# HeadsetCCup.net
KiCad netlist of a schematic drawn in EAGLE
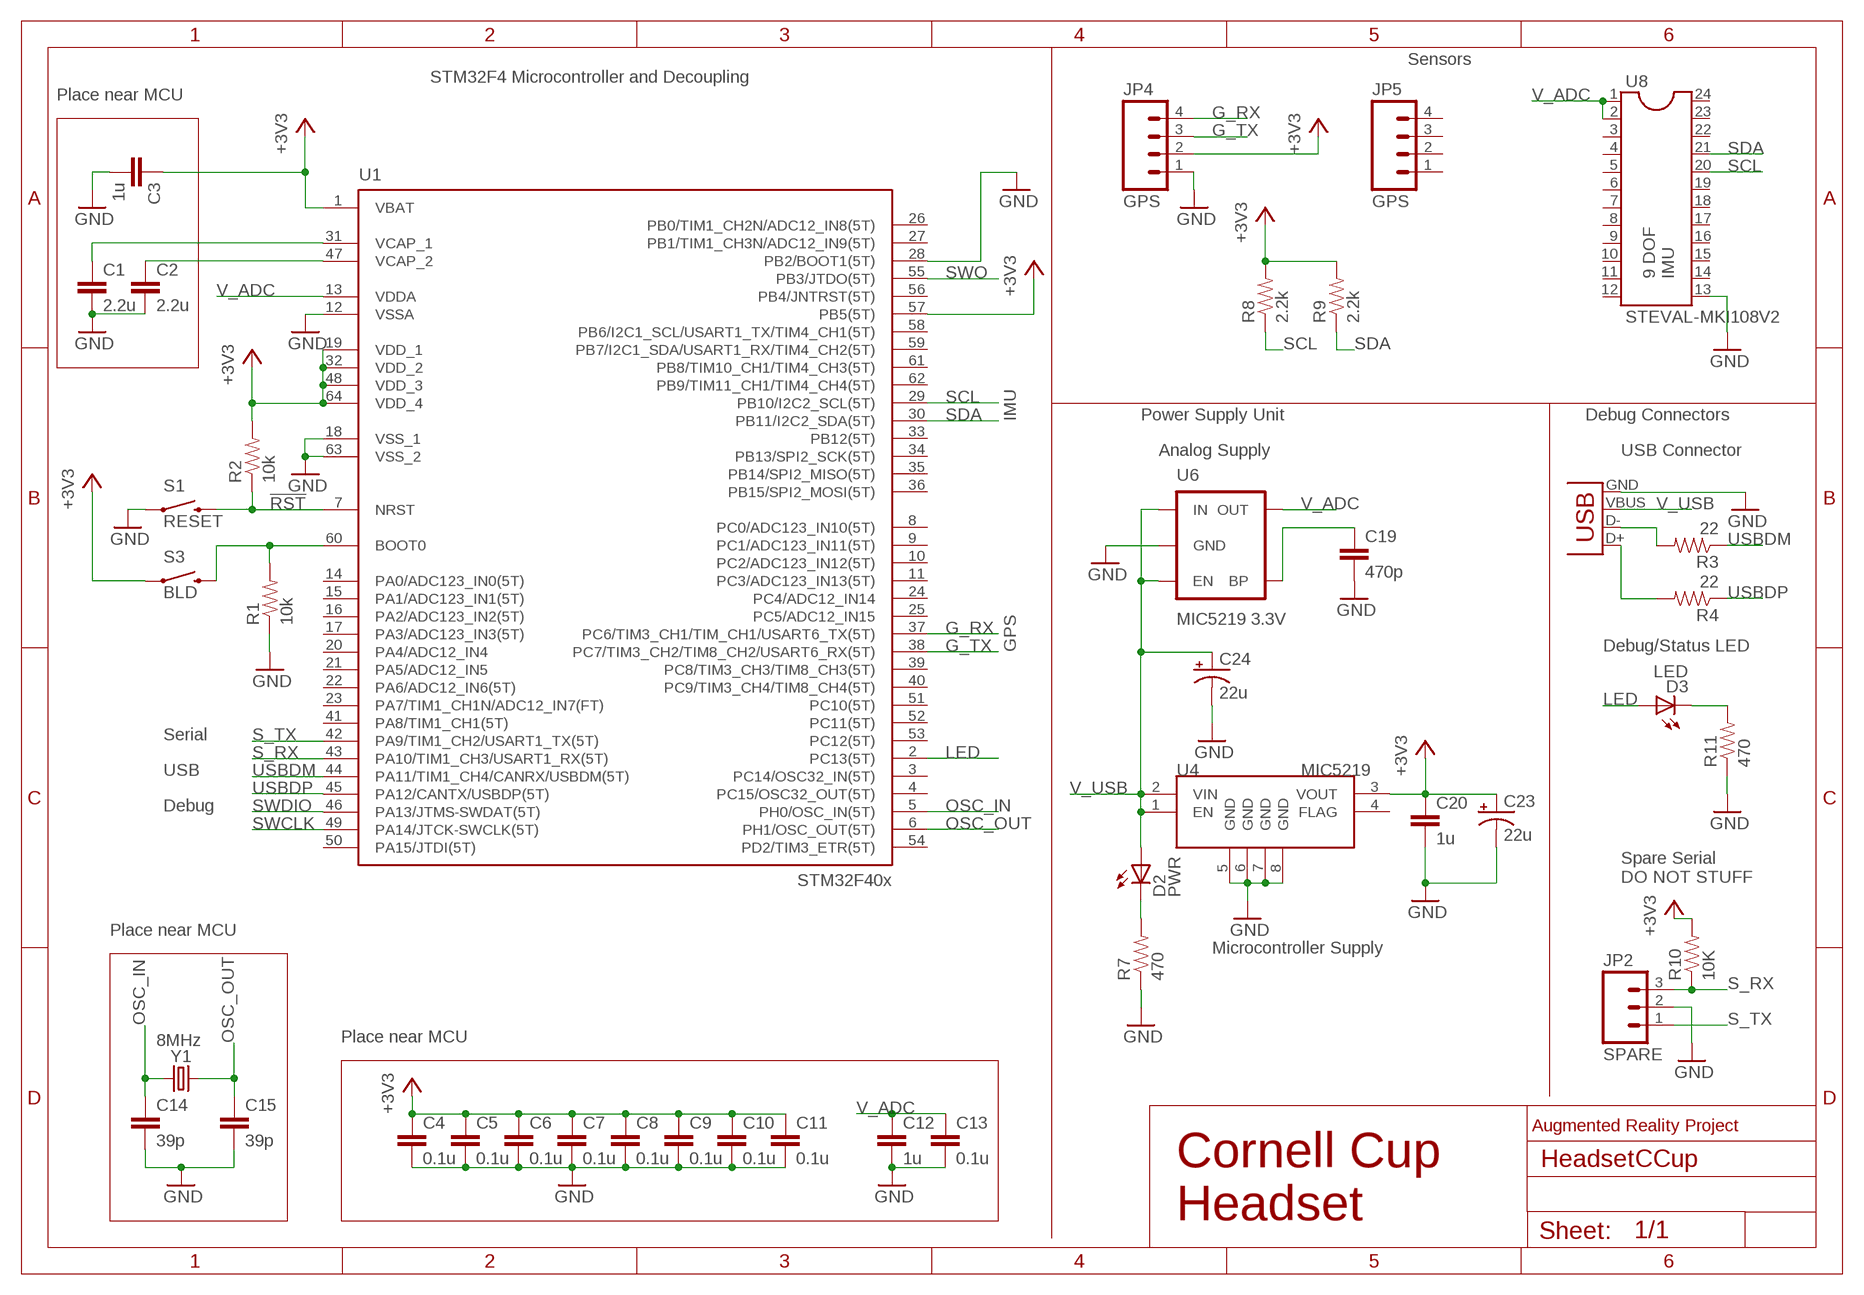
[diagram p0: schematic, sheet 1]

(export (version "E")
  (design (tool "Eeschema 10.0.6"))
  (components
    (comp (ref "C1")
      (value "2.2u")
      (footprint "eagle-import:1206")
      (libsource (lib "eagle-import") (part "CAP1206"))
    )
    (comp (ref "C2")
      (value "2.2u")
      (footprint "eagle-import:1206")
      (libsource (lib "eagle-import") (part "CAP1206"))
    )
    (comp (ref "C3")
      (value "1u")
      (footprint "eagle-import:1206")
      (libsource (lib "eagle-import") (part "CAP1206"))
    )
    (comp (ref "C4")
      (value "0.1u")
      (footprint "eagle-import:1206")
      (libsource (lib "eagle-import") (part "CAP1206"))
    )
    (comp (ref "C5")
      (value "0.1u")
      (footprint "eagle-import:1206")
      (libsource (lib "eagle-import") (part "CAP1206"))
    )
    (comp (ref "C6")
      (value "0.1u")
      (footprint "eagle-import:1206")
      (libsource (lib "eagle-import") (part "CAP1206"))
    )
    (comp (ref "C7")
      (value "0.1u")
      (footprint "eagle-import:1206")
      (libsource (lib "eagle-import") (part "CAP1206"))
    )
    (comp (ref "C8")
      (value "0.1u")
      (footprint "eagle-import:1206")
      (libsource (lib "eagle-import") (part "CAP1206"))
    )
    (comp (ref "C9")
      (value "0.1u")
      (footprint "eagle-import:1206")
      (libsource (lib "eagle-import") (part "CAP1206"))
    )
    (comp (ref "C10")
      (value "0.1u")
      (footprint "eagle-import:1206")
      (libsource (lib "eagle-import") (part "CAP1206"))
    )
    (comp (ref "C11")
      (value "0.1u")
      (footprint "eagle-import:1206")
      (libsource (lib "eagle-import") (part "CAP1206"))
    )
    (comp (ref "C12")
      (value "1u")
      (footprint "eagle-import:1206")
      (libsource (lib "eagle-import") (part "CAP1206"))
    )
    (comp (ref "C13")
      (value "0.1u")
      (footprint "eagle-import:1206")
      (libsource (lib "eagle-import") (part "CAP1206"))
    )
    (comp (ref "C14")
      (value "39p")
      (footprint "eagle-import:1206")
      (libsource (lib "eagle-import") (part "CAP1206"))
    )
    (comp (ref "C15")
      (value "39p")
      (footprint "eagle-import:1206")
      (libsource (lib "eagle-import") (part "CAP1206"))
    )
    (comp (ref "C19")
      (value "470p")
      (footprint "eagle-import:1206")
      (libsource (lib "eagle-import") (part "CAP1206"))
    )
    (comp (ref "C20")
      (value "1u")
      (footprint "eagle-import:1206")
      (libsource (lib "eagle-import") (part "CAP1206"))
    )
    (comp (ref "C23")
      (value "22u")
      (footprint "eagle-import:PANASONIC_D")
      (libsource (lib "eagle-import") (part "CAP_POLD"))
    )
    (comp (ref "C24")
      (value "22u")
      (footprint "eagle-import:PANASONIC_D")
      (libsource (lib "eagle-import") (part "CAP_POLD"))
    )
    (comp (ref "D2")
      (value "PWR")
      (footprint "eagle-import:LED-1206")
      (libsource (lib "eagle-import") (part "LED-RED1206"))
    )
    (comp (ref "D3")
      (value "LED")
      (footprint "eagle-import:LED-1206")
      (libsource (lib "eagle-import") (part "LED-RED1206"))
    )
    (comp (ref "JP1")
      (value "USBSMD")
      (footprint "eagle-import:USB-MINIB")
      (libsource (lib "eagle-import") (part "USBSMD"))
    )
    (comp (ref "JP2")
      (value "SPARE")
      (footprint "eagle-import:1X03")
      (libsource (lib "eagle-import") (part "M03PTH"))
    )
    (comp (ref "JP4")
      (value "GPS")
      (footprint "eagle-import:1X04")
      (libsource (lib "eagle-import") (part "M04PTH"))
    )
    (comp (ref "JP5")
      (value "GPS")
      (footprint "eagle-import:1X04")
      (libsource (lib "eagle-import") (part "M04PTH"))
    )
    (comp (ref "R1")
      (value "10k")
      (footprint "eagle-import:1206")
      (libsource (lib "eagle-import") (part "RES1206"))
    )
    (comp (ref "R2")
      (value "10k")
      (footprint "eagle-import:1206")
      (libsource (lib "eagle-import") (part "RES1206"))
    )
    (comp (ref "R3")
      (value "22")
      (footprint "eagle-import:1206")
      (libsource (lib "eagle-import") (part "RES1206"))
    )
    (comp (ref "R4")
      (value "22")
      (footprint "eagle-import:1206")
      (libsource (lib "eagle-import") (part "RES1206"))
    )
    (comp (ref "R7")
      (value "470")
      (footprint "eagle-import:1206")
      (libsource (lib "eagle-import") (part "RES1206"))
    )
    (comp (ref "R8")
      (value "2.2k")
      (footprint "eagle-import:1206")
      (libsource (lib "eagle-import") (part "RES1206"))
    )
    (comp (ref "R9")
      (value "2.2k")
      (footprint "eagle-import:1206")
      (libsource (lib "eagle-import") (part "RES1206"))
    )
    (comp (ref "R10")
      (value "10K")
      (footprint "eagle-import:1206")
      (libsource (lib "eagle-import") (part "RES1206"))
    )
    (comp (ref "R11")
      (value "470")
      (footprint "eagle-import:1206")
      (libsource (lib "eagle-import") (part "RES1206"))
    )
    (comp (ref "S1")
      (value "RESET")
      (footprint "eagle-import:TACTILE-PTH")
      (libsource (lib "eagle-import") (part "SWITCH-MOMENTARY-2PTH"))
    )
    (comp (ref "S3")
      (value "BLD")
      (footprint "eagle-import:TACTILE-PTH")
      (libsource (lib "eagle-import") (part "SWITCH-MOMENTARY-2PTH"))
    )
    (comp (ref "U1")
      (value "STM32F405RGT6")
      (footprint "eagle-import:TQFP64")
      (libsource (lib "eagle-import") (part "STM32F405R"))
    )
    (comp (ref "U4")
      (value "MIC5219")
      (footprint "eagle-import:MSOP8")
      (libsource (lib "eagle-import") (part "V_REG_MIC5216"))
    )
    (comp (ref "U6")
      (value "MIC5219 3.3V")
      (footprint "eagle-import:SOT23-5")
      (libsource (lib "eagle-import") (part "V_REG_MIC52193.3V"))
    )
    (comp (ref "U8")
      (value "STEVAL-MKI108V2")
      (footprint "eagle-import:DIL24-6")
      (libsource (lib "eagle-import") (part "DIL24-6"))
    )
    (comp (ref "Y1")
      (value "8MHz")
      (footprint "eagle-import:HC49US")
      (libsource (lib "eagle-import") (part "CRYSTALHC49US"))
    )
  )
  (nets
    (net (code "1") (name "+3V3") (class "Default")
      (node (ref "C10") (pin "1") (pinfunction "1_1") (pintype "passive"))
      (node (ref "C11") (pin "1") (pinfunction "1_1") (pintype "passive"))
      (node (ref "C20") (pin "1") (pinfunction "1_1") (pintype "passive"))
      (node (ref "C23") (pin "+") (pinfunction "+_+") (pintype "passive"))
      (node (ref "C3") (pin "1") (pinfunction "1_1") (pintype "passive"))
      (node (ref "C4") (pin "1") (pinfunction "1_1") (pintype "passive"))
      (node (ref "C5") (pin "1") (pinfunction "1_1") (pintype "passive"))
      (node (ref "C6") (pin "1") (pinfunction "1_1") (pintype "passive"))
      (node (ref "C7") (pin "1") (pinfunction "1_1") (pintype "passive"))
      (node (ref "C8") (pin "1") (pinfunction "1_1") (pintype "passive"))
      (node (ref "C9") (pin "1") (pinfunction "1_1") (pintype "passive"))
      (node (ref "JP4") (pin "2") (pinfunction "2_2") (pintype "passive"))
      (node (ref "R10") (pin "2") (pinfunction "2_2") (pintype "passive"))
      (node (ref "R2") (pin "2") (pinfunction "2_2") (pintype "passive"))
      (node (ref "R8") (pin "2") (pinfunction "2_2") (pintype "passive"))
      (node (ref "R9") (pin "2") (pinfunction "2_2") (pintype "passive"))
      (node (ref "S3") (pin "1") (pinfunction "1_1") (pintype "passive"))
      (node (ref "U1") (pin "1") (pinfunction "VBAT_1") (pintype "bidirectional"))
      (node (ref "U1") (pin "19") (pinfunction "VDD_1_19") (pintype "bidirectional"))
      (node (ref "U1") (pin "32") (pinfunction "VDD_2_32") (pintype "bidirectional"))
      (node (ref "U1") (pin "48") (pinfunction "VDD_3_48") (pintype "bidirectional"))
      (node (ref "U1") (pin "57") (pinfunction "PB5(5T)_57") (pintype "bidirectional"))
      (node (ref "U1") (pin "64") (pinfunction "VDD_4_64") (pintype "bidirectional"))
      (node (ref "U4") (pin "3") (pinfunction "VOUT_3") (pintype "bidirectional"))
    )
    (net (code "2") (name "/G_RX") (class "Default")
      (node (ref "JP4") (pin "4") (pinfunction "4_4") (pintype "passive"))
      (node (ref "U1") (pin "37") (pinfunction "PC6/TIM3_CH1/TIM_CH1/USART6_TX(5T)_37") (pintype "bidirectional"))
    )
    (net (code "3") (name "/G_TX") (class "Default")
      (node (ref "JP4") (pin "3") (pinfunction "3_3") (pintype "passive"))
      (node (ref "U1") (pin "38") (pinfunction "PC7/TIM3_CH2/TIM8_CH2/USART6_RX(5T)_38") (pintype "bidirectional"))
    )
    (net (code "4") (name "/LED") (class "Default")
      (node (ref "D3") (pin "A") (pinfunction "A_A") (pintype "passive"))
      (node (ref "U1") (pin "2") (pinfunction "PC13(5T)_2") (pintype "bidirectional"))
    )
    (net (code "5") (name "/OSC_IN") (class "Default")
      (node (ref "C14") (pin "1") (pinfunction "1_1") (pintype "passive"))
      (node (ref "U1") (pin "5") (pinfunction "PH0/OSC_IN(5T)_5") (pintype "bidirectional"))
      (node (ref "Y1") (pin "1") (pinfunction "1_1") (pintype "passive"))
    )
    (net (code "6") (name "/OSC_OUT") (class "Default")
      (node (ref "C15") (pin "1") (pinfunction "1_1") (pintype "passive"))
      (node (ref "U1") (pin "6") (pinfunction "PH1/OSC_OUT(5T)_6") (pintype "bidirectional"))
      (node (ref "Y1") (pin "2") (pinfunction "2_2") (pintype "passive"))
    )
    (net (code "7") (name "/SCL") (class "Default")
      (node (ref "R8") (pin "1") (pinfunction "1_1") (pintype "passive"))
      (node (ref "U1") (pin "29") (pinfunction "PB10/I2C2_SCL(5T)_29") (pintype "bidirectional"))
      (node (ref "U8") (pin "20") (pinfunction "20_20") (pintype "passive"))
    )
    (net (code "8") (name "/SDA") (class "Default")
      (node (ref "R9") (pin "1") (pinfunction "1_1") (pintype "passive"))
      (node (ref "U1") (pin "30") (pinfunction "PB11/I2C2_SDA(5T)_30") (pintype "bidirectional"))
      (node (ref "U8") (pin "21") (pinfunction "21_21") (pintype "passive"))
    )
    (net (code "9") (name "/SWCLK") (class "Default")
      (node (ref "U1") (pin "49") (pinfunction "PA14/JTCK-SWCLK(5T)_49") (pintype "bidirectional"))
    )
    (net (code "10") (name "/SWDIO") (class "Default")
      (node (ref "U1") (pin "46") (pinfunction "PA13/JTMS-SWDAT(5T)_46") (pintype "bidirectional"))
    )
    (net (code "11") (name "/SWO") (class "Default")
      (node (ref "U1") (pin "55") (pinfunction "PB3/JTDO(5T)_55") (pintype "bidirectional"))
    )
    (net (code "12") (name "/S_RX") (class "Default")
      (node (ref "JP2") (pin "3") (pinfunction "3_3") (pintype "passive"))
      (node (ref "R10") (pin "1") (pinfunction "1_1") (pintype "passive"))
      (node (ref "U1") (pin "43") (pinfunction "PA10/TIM1_CH3/USART1_RX(5T)_43") (pintype "bidirectional"))
    )
    (net (code "13") (name "/S_TX") (class "Default")
      (node (ref "JP2") (pin "1") (pinfunction "1_1") (pintype "passive"))
      (node (ref "U1") (pin "42") (pinfunction "PA9/TIM1_CH2/USART1_TX(5T)_42") (pintype "bidirectional"))
    )
    (net (code "14") (name "/USBDM") (class "Default")
      (node (ref "R3") (pin "1") (pinfunction "1_1") (pintype "passive"))
      (node (ref "U1") (pin "44") (pinfunction "PA11/TIM1_CH4/CANRX/USBDM(5T)_44") (pintype "bidirectional"))
    )
    (net (code "15") (name "/USBDP") (class "Default")
      (node (ref "R4") (pin "1") (pinfunction "1_1") (pintype "passive"))
      (node (ref "U1") (pin "45") (pinfunction "PA12/CANTX/USBDP(5T)_45") (pintype "bidirectional"))
    )
    (net (code "16") (name "/V_ADC") (class "Default")
      (node (ref "C12") (pin "1") (pinfunction "1_1") (pintype "passive"))
      (node (ref "C13") (pin "1") (pinfunction "1_1") (pintype "passive"))
      (node (ref "U1") (pin "13") (pinfunction "VDDA_13") (pintype "bidirectional"))
      (node (ref "U6") (pin "5") (pinfunction "OUT_5") (pintype "passive"))
      (node (ref "U8") (pin "1") (pinfunction "1_1") (pintype "passive"))
      (node (ref "U8") (pin "2") (pinfunction "2_2") (pintype "passive"))
    )
    (net (code "17") (name "/V_USB") (class "Default")
      (node (ref "C24") (pin "+") (pinfunction "+_+") (pintype "passive"))
      (node (ref "D2") (pin "A") (pinfunction "A_A") (pintype "passive"))
      (node (ref "JP1") (pin "VBUS") (pinfunction "VBUS_VBUS") (pintype "bidirectional"))
      (node (ref "U4") (pin "1") (pinfunction "EN_1") (pintype "bidirectional"))
      (node (ref "U4") (pin "2") (pinfunction "VIN_2") (pintype "bidirectional"))
      (node (ref "U6") (pin "1") (pinfunction "IN_1") (pintype "input"))
      (node (ref "U6") (pin "3") (pinfunction "EN_3") (pintype "input"))
    )
    (net (code "18") (name "/~{RST}") (class "Default")
      (node (ref "R2") (pin "1") (pinfunction "1_1") (pintype "passive"))
      (node (ref "S1") (pin "3") (pinfunction "2_3") (pintype "passive"))
      (node (ref "U1") (pin "7") (pinfunction "NRST_7") (pintype "bidirectional"))
    )
    (net (code "19") (name "GND") (class "Default")
      (node (ref "C1") (pin "2") (pinfunction "2_2") (pintype "passive"))
      (node (ref "C10") (pin "2") (pinfunction "2_2") (pintype "passive"))
      (node (ref "C11") (pin "2") (pinfunction "2_2") (pintype "passive"))
      (node (ref "C12") (pin "2") (pinfunction "2_2") (pintype "passive"))
      (node (ref "C13") (pin "2") (pinfunction "2_2") (pintype "passive"))
      (node (ref "C14") (pin "2") (pinfunction "2_2") (pintype "passive"))
      (node (ref "C15") (pin "2") (pinfunction "2_2") (pintype "passive"))
      (node (ref "C19") (pin "2") (pinfunction "2_2") (pintype "passive"))
      (node (ref "C2") (pin "2") (pinfunction "2_2") (pintype "passive"))
      (node (ref "C20") (pin "2") (pinfunction "2_2") (pintype "passive"))
      (node (ref "C23") (pin "-") (pinfunction "-_-") (pintype "passive"))
      (node (ref "C24") (pin "-") (pinfunction "-_-") (pintype "passive"))
      (node (ref "C3") (pin "2") (pinfunction "2_2") (pintype "passive"))
      (node (ref "C4") (pin "2") (pinfunction "2_2") (pintype "passive"))
      (node (ref "C5") (pin "2") (pinfunction "2_2") (pintype "passive"))
      (node (ref "C6") (pin "2") (pinfunction "2_2") (pintype "passive"))
      (node (ref "C7") (pin "2") (pinfunction "2_2") (pintype "passive"))
      (node (ref "C8") (pin "2") (pinfunction "2_2") (pintype "passive"))
      (node (ref "C9") (pin "2") (pinfunction "2_2") (pintype "passive"))
      (node (ref "JP1") (pin "GND") (pinfunction "GND_GND") (pintype "bidirectional"))
      (node (ref "JP2") (pin "2") (pinfunction "2_2") (pintype "passive"))
      (node (ref "JP4") (pin "1") (pinfunction "1_1") (pintype "passive"))
      (node (ref "R1") (pin "1") (pinfunction "1_1") (pintype "passive"))
      (node (ref "R11") (pin "1") (pinfunction "1_1") (pintype "passive"))
      (node (ref "R7") (pin "1") (pinfunction "1_1") (pintype "passive"))
      (node (ref "S1") (pin "1") (pinfunction "1_1") (pintype "passive"))
      (node (ref "U1") (pin "12") (pinfunction "VSSA_12") (pintype "bidirectional"))
      (node (ref "U1") (pin "18") (pinfunction "VSS_1_18") (pintype "bidirectional"))
      (node (ref "U1") (pin "28") (pinfunction "PB2/BOOT1(5T)_28") (pintype "bidirectional"))
      (node (ref "U1") (pin "63") (pinfunction "VSS_2_63") (pintype "bidirectional"))
      (node (ref "U4") (pin "5") (pinfunction "GND_5") (pintype "bidirectional"))
      (node (ref "U4") (pin "6") (pinfunction "GND_6") (pintype "bidirectional"))
      (node (ref "U4") (pin "7") (pinfunction "GND_7") (pintype "bidirectional"))
      (node (ref "U4") (pin "8") (pinfunction "GND_8") (pintype "bidirectional"))
      (node (ref "U6") (pin "2") (pinfunction "GND_2") (pintype "input"))
      (node (ref "U8") (pin "13") (pinfunction "13_13") (pintype "passive"))
    )
    (net (code "20") (name "Net-(D2-PadC)") (class "Default")
      (node (ref "D2") (pin "C") (pinfunction "C_C") (pintype "passive"))
      (node (ref "R7") (pin "2") (pinfunction "2_2") (pintype "passive"))
    )
    (net (code "21") (name "Net-(D3-PadC)") (class "Default")
      (node (ref "D3") (pin "C") (pinfunction "C_C") (pintype "passive"))
      (node (ref "R11") (pin "2") (pinfunction "2_2") (pintype "passive"))
    )
    (net (code "22") (name "Net-(JP1-PadD+)") (class "Default")
      (node (ref "JP1") (pin "D+") (pinfunction "D+_D+") (pintype "bidirectional"))
      (node (ref "R4") (pin "2") (pinfunction "2_2") (pintype "passive"))
    )
    (net (code "23") (name "Net-(JP1-PadD-)") (class "Default")
      (node (ref "JP1") (pin "D-") (pinfunction "D-_D-") (pintype "bidirectional"))
      (node (ref "R3") (pin "2") (pinfunction "2_2") (pintype "passive"))
    )
    (net (code "24") (name "Net-(S3-2)") (class "Default")
      (node (ref "R1") (pin "2") (pinfunction "2_2") (pintype "passive"))
      (node (ref "S3") (pin "3") (pinfunction "2_3") (pintype "passive"))
      (node (ref "U1") (pin "60") (pinfunction "BOOT0_60") (pintype "bidirectional"))
    )
    (net (code "25") (name "Net-(U1-VCAP_1)") (class "Default")
      (node (ref "C1") (pin "1") (pinfunction "1_1") (pintype "passive"))
      (node (ref "U1") (pin "31") (pinfunction "VCAP_1_31") (pintype "bidirectional"))
    )
    (net (code "26") (name "Net-(U1-VCAP_2)") (class "Default")
      (node (ref "C2") (pin "1") (pinfunction "1_1") (pintype "passive"))
      (node (ref "U1") (pin "47") (pinfunction "VCAP_2_47") (pintype "bidirectional"))
    )
    (net (code "27") (name "Net-(U6-BP)") (class "Default")
      (node (ref "C19") (pin "1") (pinfunction "1_1") (pintype "passive"))
      (node (ref "U6") (pin "4") (pinfunction "BP_4") (pintype "input"))
    )
    (net (code "28") (name "unconnected-(JP5-Pad1)") (class "Default")
      (node (ref "JP5") (pin "1") (pinfunction "1_1") (pintype "passive"))
    )
    (net (code "29") (name "unconnected-(JP5-Pad2)") (class "Default")
      (node (ref "JP5") (pin "2") (pinfunction "2_2") (pintype "passive"))
    )
    (net (code "30") (name "unconnected-(JP5-Pad3)") (class "Default")
      (node (ref "JP5") (pin "3") (pinfunction "3_3") (pintype "passive"))
    )
    (net (code "31") (name "unconnected-(JP5-Pad4)") (class "Default")
      (node (ref "JP5") (pin "4") (pinfunction "4_4") (pintype "passive"))
    )
    (net (code "32") (name "unconnected-(U1-PA0{slash}ADC123_IN0(5T)-Pad14)") (class "Default")
      (node (ref "U1") (pin "14") (pinfunction "PA0/ADC123_IN0(5T)_14") (pintype "bidirectional"))
    )
    (net (code "33") (name "unconnected-(U1-PA1{slash}ADC123_IN1(5T)-Pad15)") (class "Default")
      (node (ref "U1") (pin "15") (pinfunction "PA1/ADC123_IN1(5T)_15") (pintype "bidirectional"))
    )
    (net (code "34") (name "unconnected-(U1-PA2{slash}ADC123_IN2(5T)-Pad16)") (class "Default")
      (node (ref "U1") (pin "16") (pinfunction "PA2/ADC123_IN2(5T)_16") (pintype "bidirectional"))
    )
    (net (code "35") (name "unconnected-(U1-PA3{slash}ADC123_IN3(5T)-Pad17)") (class "Default")
      (node (ref "U1") (pin "17") (pinfunction "PA3/ADC123_IN3(5T)_17") (pintype "bidirectional"))
    )
    (net (code "36") (name "unconnected-(U1-PA4{slash}ADC12_IN4-Pad20)") (class "Default")
      (node (ref "U1") (pin "20") (pinfunction "PA4/ADC12_IN4_20") (pintype "bidirectional"))
    )
    (net (code "37") (name "unconnected-(U1-PA5{slash}ADC12_IN5-Pad21)") (class "Default")
      (node (ref "U1") (pin "21") (pinfunction "PA5/ADC12_IN5_21") (pintype "bidirectional"))
    )
    (net (code "38") (name "unconnected-(U1-PA6{slash}ADC12_IN6(5T)-Pad22)") (class "Default")
      (node (ref "U1") (pin "22") (pinfunction "PA6/ADC12_IN6(5T)_22") (pintype "bidirectional"))
    )
    (net (code "39") (name "unconnected-(U1-PA7{slash}TIM1_CH1N{slash}ADC12_IN7(FT)-Pad23)") (class "Default")
      (node (ref "U1") (pin "23") (pinfunction "PA7/TIM1_CH1N/ADC12_IN7(FT)_23") (pintype "bidirectional"))
    )
    (net (code "40") (name "unconnected-(U1-PA8{slash}TIM1_CH1(5T)-Pad41)") (class "Default")
      (node (ref "U1") (pin "41") (pinfunction "PA8/TIM1_CH1(5T)_41") (pintype "bidirectional"))
    )
    (net (code "41") (name "unconnected-(U1-PA15{slash}JTDI(5T)-Pad50)") (class "Default")
      (node (ref "U1") (pin "50") (pinfunction "PA15/JTDI(5T)_50") (pintype "bidirectional"))
    )
    (net (code "42") (name "unconnected-(U1-PB0{slash}TIM1_CH2N{slash}ADC12_IN8(5T)-Pad26)") (class "Default")
      (node (ref "U1") (pin "26") (pinfunction "PB0/TIM1_CH2N/ADC12_IN8(5T)_26") (pintype "bidirectional"))
    )
    (net (code "43") (name "unconnected-(U1-PB1{slash}TIM1_CH3N{slash}ADC12_IN9(5T)-Pad27)") (class "Default")
      (node (ref "U1") (pin "27") (pinfunction "PB1/TIM1_CH3N/ADC12_IN9(5T)_27") (pintype "bidirectional"))
    )
    (net (code "44") (name "unconnected-(U1-PB4{slash}JNTRST(5T)-Pad56)") (class "Default")
      (node (ref "U1") (pin "56") (pinfunction "PB4/JNTRST(5T)_56") (pintype "bidirectional"))
    )
    (net (code "45") (name "unconnected-(U1-PB6{slash}I2C1_SCL{slash}USART1_TX{slash}TIM4_CH1(5T)-Pad58)") (class "Default")
      (node (ref "U1") (pin "58") (pinfunction "PB6/I2C1_SCL/USART1_TX/TIM4_CH1(5T)_58") (pintype "bidirectional"))
    )
    (net (code "46") (name "unconnected-(U1-PB7{slash}I2C1_SDA{slash}USART1_RX{slash}TIM4_CH2(5T)-Pad59)") (class "Default")
      (node (ref "U1") (pin "59") (pinfunction "PB7/I2C1_SDA/USART1_RX/TIM4_CH2(5T)_59") (pintype "bidirectional"))
    )
    (net (code "47") (name "unconnected-(U1-PB8{slash}TIM10_CH1{slash}TIM4_CH3(5T)-Pad61)") (class "Default")
      (node (ref "U1") (pin "61") (pinfunction "PB8/TIM10_CH1/TIM4_CH3(5T)_61") (pintype "bidirectional"))
    )
    (net (code "48") (name "unconnected-(U1-PB9{slash}TIM11_CH1{slash}TIM4_CH4(5T)-Pad62)") (class "Default")
      (node (ref "U1") (pin "62") (pinfunction "PB9/TIM11_CH1/TIM4_CH4(5T)_62") (pintype "bidirectional"))
    )
    (net (code "49") (name "unconnected-(U1-PB12(5T)-Pad33)") (class "Default")
      (node (ref "U1") (pin "33") (pinfunction "PB12(5T)_33") (pintype "bidirectional"))
    )
    (net (code "50") (name "unconnected-(U1-PB13{slash}SPI2_SCK(5T)-Pad34)") (class "Default")
      (node (ref "U1") (pin "34") (pinfunction "PB13/SPI2_SCK(5T)_34") (pintype "bidirectional"))
    )
    (net (code "51") (name "unconnected-(U1-PB14{slash}SPI2_MISO(5T)-Pad35)") (class "Default")
      (node (ref "U1") (pin "35") (pinfunction "PB14/SPI2_MISO(5T)_35") (pintype "bidirectional"))
    )
    (net (code "52") (name "unconnected-(U1-PB15{slash}SPI2_MOSI(5T)-Pad36)") (class "Default")
      (node (ref "U1") (pin "36") (pinfunction "PB15/SPI2_MOSI(5T)_36") (pintype "bidirectional"))
    )
    (net (code "53") (name "unconnected-(U1-PC0{slash}ADC123_IN10(5T)-Pad8)") (class "Default")
      (node (ref "U1") (pin "8") (pinfunction "PC0/ADC123_IN10(5T)_8") (pintype "bidirectional"))
    )
    (net (code "54") (name "unconnected-(U1-PC1{slash}ADC123_IN11(5T)-Pad9)") (class "Default")
      (node (ref "U1") (pin "9") (pinfunction "PC1/ADC123_IN11(5T)_9") (pintype "bidirectional"))
    )
    (net (code "55") (name "unconnected-(U1-PC2{slash}ADC123_IN12(5T)-Pad10)") (class "Default")
      (node (ref "U1") (pin "10") (pinfunction "PC2/ADC123_IN12(5T)_10") (pintype "bidirectional"))
    )
    (net (code "56") (name "unconnected-(U1-PC3{slash}ADC123_IN13(5T)-Pad11)") (class "Default")
      (node (ref "U1") (pin "11") (pinfunction "PC3/ADC123_IN13(5T)_11") (pintype "bidirectional"))
    )
    (net (code "57") (name "unconnected-(U1-PC4{slash}ADC12_IN14-Pad24)") (class "Default")
      (node (ref "U1") (pin "24") (pinfunction "PC4/ADC12_IN14_24") (pintype "bidirectional"))
    )
    (net (code "58") (name "unconnected-(U1-PC5{slash}ADC12_IN15-Pad25)") (class "Default")
      (node (ref "U1") (pin "25") (pinfunction "PC5/ADC12_IN15_25") (pintype "bidirectional"))
    )
    (net (code "59") (name "unconnected-(U1-PC8{slash}TIM3_CH3{slash}TIM8_CH3(5T)-Pad39)") (class "Default")
      (node (ref "U1") (pin "39") (pinfunction "PC8/TIM3_CH3/TIM8_CH3(5T)_39") (pintype "bidirectional"))
    )
    (net (code "60") (name "unconnected-(U1-PC9{slash}TIM3_CH4{slash}TIM8_CH4(5T)-Pad40)") (class "Default")
      (node (ref "U1") (pin "40") (pinfunction "PC9/TIM3_CH4/TIM8_CH4(5T)_40") (pintype "bidirectional"))
    )
    (net (code "61") (name "unconnected-(U1-PC10(5T)-Pad51)") (class "Default")
      (node (ref "U1") (pin "51") (pinfunction "PC10(5T)_51") (pintype "bidirectional"))
    )
    (net (code "62") (name "unconnected-(U1-PC11(5T)-Pad52)") (class "Default")
      (node (ref "U1") (pin "52") (pinfunction "PC11(5T)_52") (pintype "bidirectional"))
    )
    (net (code "63") (name "unconnected-(U1-PC12(5T)-Pad53)") (class "Default")
      (node (ref "U1") (pin "53") (pinfunction "PC12(5T)_53") (pintype "bidirectional"))
    )
    (net (code "64") (name "unconnected-(U1-PC14{slash}OSC32_IN(5T)-Pad3)") (class "Default")
      (node (ref "U1") (pin "3") (pinfunction "PC14/OSC32_IN(5T)_3") (pintype "bidirectional"))
    )
    (net (code "65") (name "unconnected-(U1-PC15{slash}OSC32_OUT(5T)-Pad4)") (class "Default")
      (node (ref "U1") (pin "4") (pinfunction "PC15/OSC32_OUT(5T)_4") (pintype "bidirectional"))
    )
    (net (code "66") (name "unconnected-(U1-PD2{slash}TIM3_ETR(5T)-Pad54)") (class "Default")
      (node (ref "U1") (pin "54") (pinfunction "PD2/TIM3_ETR(5T)_54") (pintype "bidirectional"))
    )
    (net (code "67") (name "unconnected-(U4-FLAG-Pad4)") (class "Default")
      (node (ref "U4") (pin "4") (pinfunction "FLAG_4") (pintype "bidirectional"))
    )
    (net (code "68") (name "unconnected-(U8-Pad3)") (class "Default")
      (node (ref "U8") (pin "3") (pinfunction "3_3") (pintype "passive"))
    )
    (net (code "69") (name "unconnected-(U8-Pad4)") (class "Default")
      (node (ref "U8") (pin "4") (pinfunction "4_4") (pintype "passive"))
    )
    (net (code "70") (name "unconnected-(U8-Pad5)") (class "Default")
      (node (ref "U8") (pin "5") (pinfunction "5_5") (pintype "passive"))
    )
    (net (code "71") (name "unconnected-(U8-Pad6)") (class "Default")
      (node (ref "U8") (pin "6") (pinfunction "6_6") (pintype "passive"))
    )
    (net (code "72") (name "unconnected-(U8-Pad7)") (class "Default")
      (node (ref "U8") (pin "7") (pinfunction "7_7") (pintype "passive"))
    )
    (net (code "73") (name "unconnected-(U8-Pad8)") (class "Default")
      (node (ref "U8") (pin "8") (pinfunction "8_8") (pintype "passive"))
    )
    (net (code "74") (name "unconnected-(U8-Pad9)") (class "Default")
      (node (ref "U8") (pin "9") (pinfunction "9_9") (pintype "passive"))
    )
    (net (code "75") (name "unconnected-(U8-Pad10)") (class "Default")
      (node (ref "U8") (pin "10") (pinfunction "10_10") (pintype "passive"))
    )
    (net (code "76") (name "unconnected-(U8-Pad11)") (class "Default")
      (node (ref "U8") (pin "11") (pinfunction "11_11") (pintype "passive"))
    )
    (net (code "77") (name "unconnected-(U8-Pad12)") (class "Default")
      (node (ref "U8") (pin "12") (pinfunction "12_12") (pintype "passive"))
    )
    (net (code "78") (name "unconnected-(U8-Pad14)") (class "Default")
      (node (ref "U8") (pin "14") (pinfunction "14_14") (pintype "passive"))
    )
    (net (code "79") (name "unconnected-(U8-Pad15)") (class "Default")
      (node (ref "U8") (pin "15") (pinfunction "15_15") (pintype "passive"))
    )
    (net (code "80") (name "unconnected-(U8-Pad16)") (class "Default")
      (node (ref "U8") (pin "16") (pinfunction "16_16") (pintype "passive"))
    )
    (net (code "81") (name "unconnected-(U8-Pad17)") (class "Default")
      (node (ref "U8") (pin "17") (pinfunction "17_17") (pintype "passive"))
    )
    (net (code "82") (name "unconnected-(U8-Pad18)") (class "Default")
      (node (ref "U8") (pin "18") (pinfunction "18_18") (pintype "passive"))
    )
    (net (code "83") (name "unconnected-(U8-Pad19)") (class "Default")
      (node (ref "U8") (pin "19") (pinfunction "19_19") (pintype "passive"))
    )
    (net (code "84") (name "unconnected-(U8-Pad22)") (class "Default")
      (node (ref "U8") (pin "22") (pinfunction "22_22") (pintype "passive"))
    )
    (net (code "85") (name "unconnected-(U8-Pad23)") (class "Default")
      (node (ref "U8") (pin "23") (pinfunction "23_23") (pintype "passive"))
    )
    (net (code "86") (name "unconnected-(U8-Pad24)") (class "Default")
      (node (ref "U8") (pin "24") (pinfunction "24_24") (pintype "passive"))
    )
  )
)
